# kezpad_SCH.net
KiCad netlist of a schematic drawn in EasyEDA
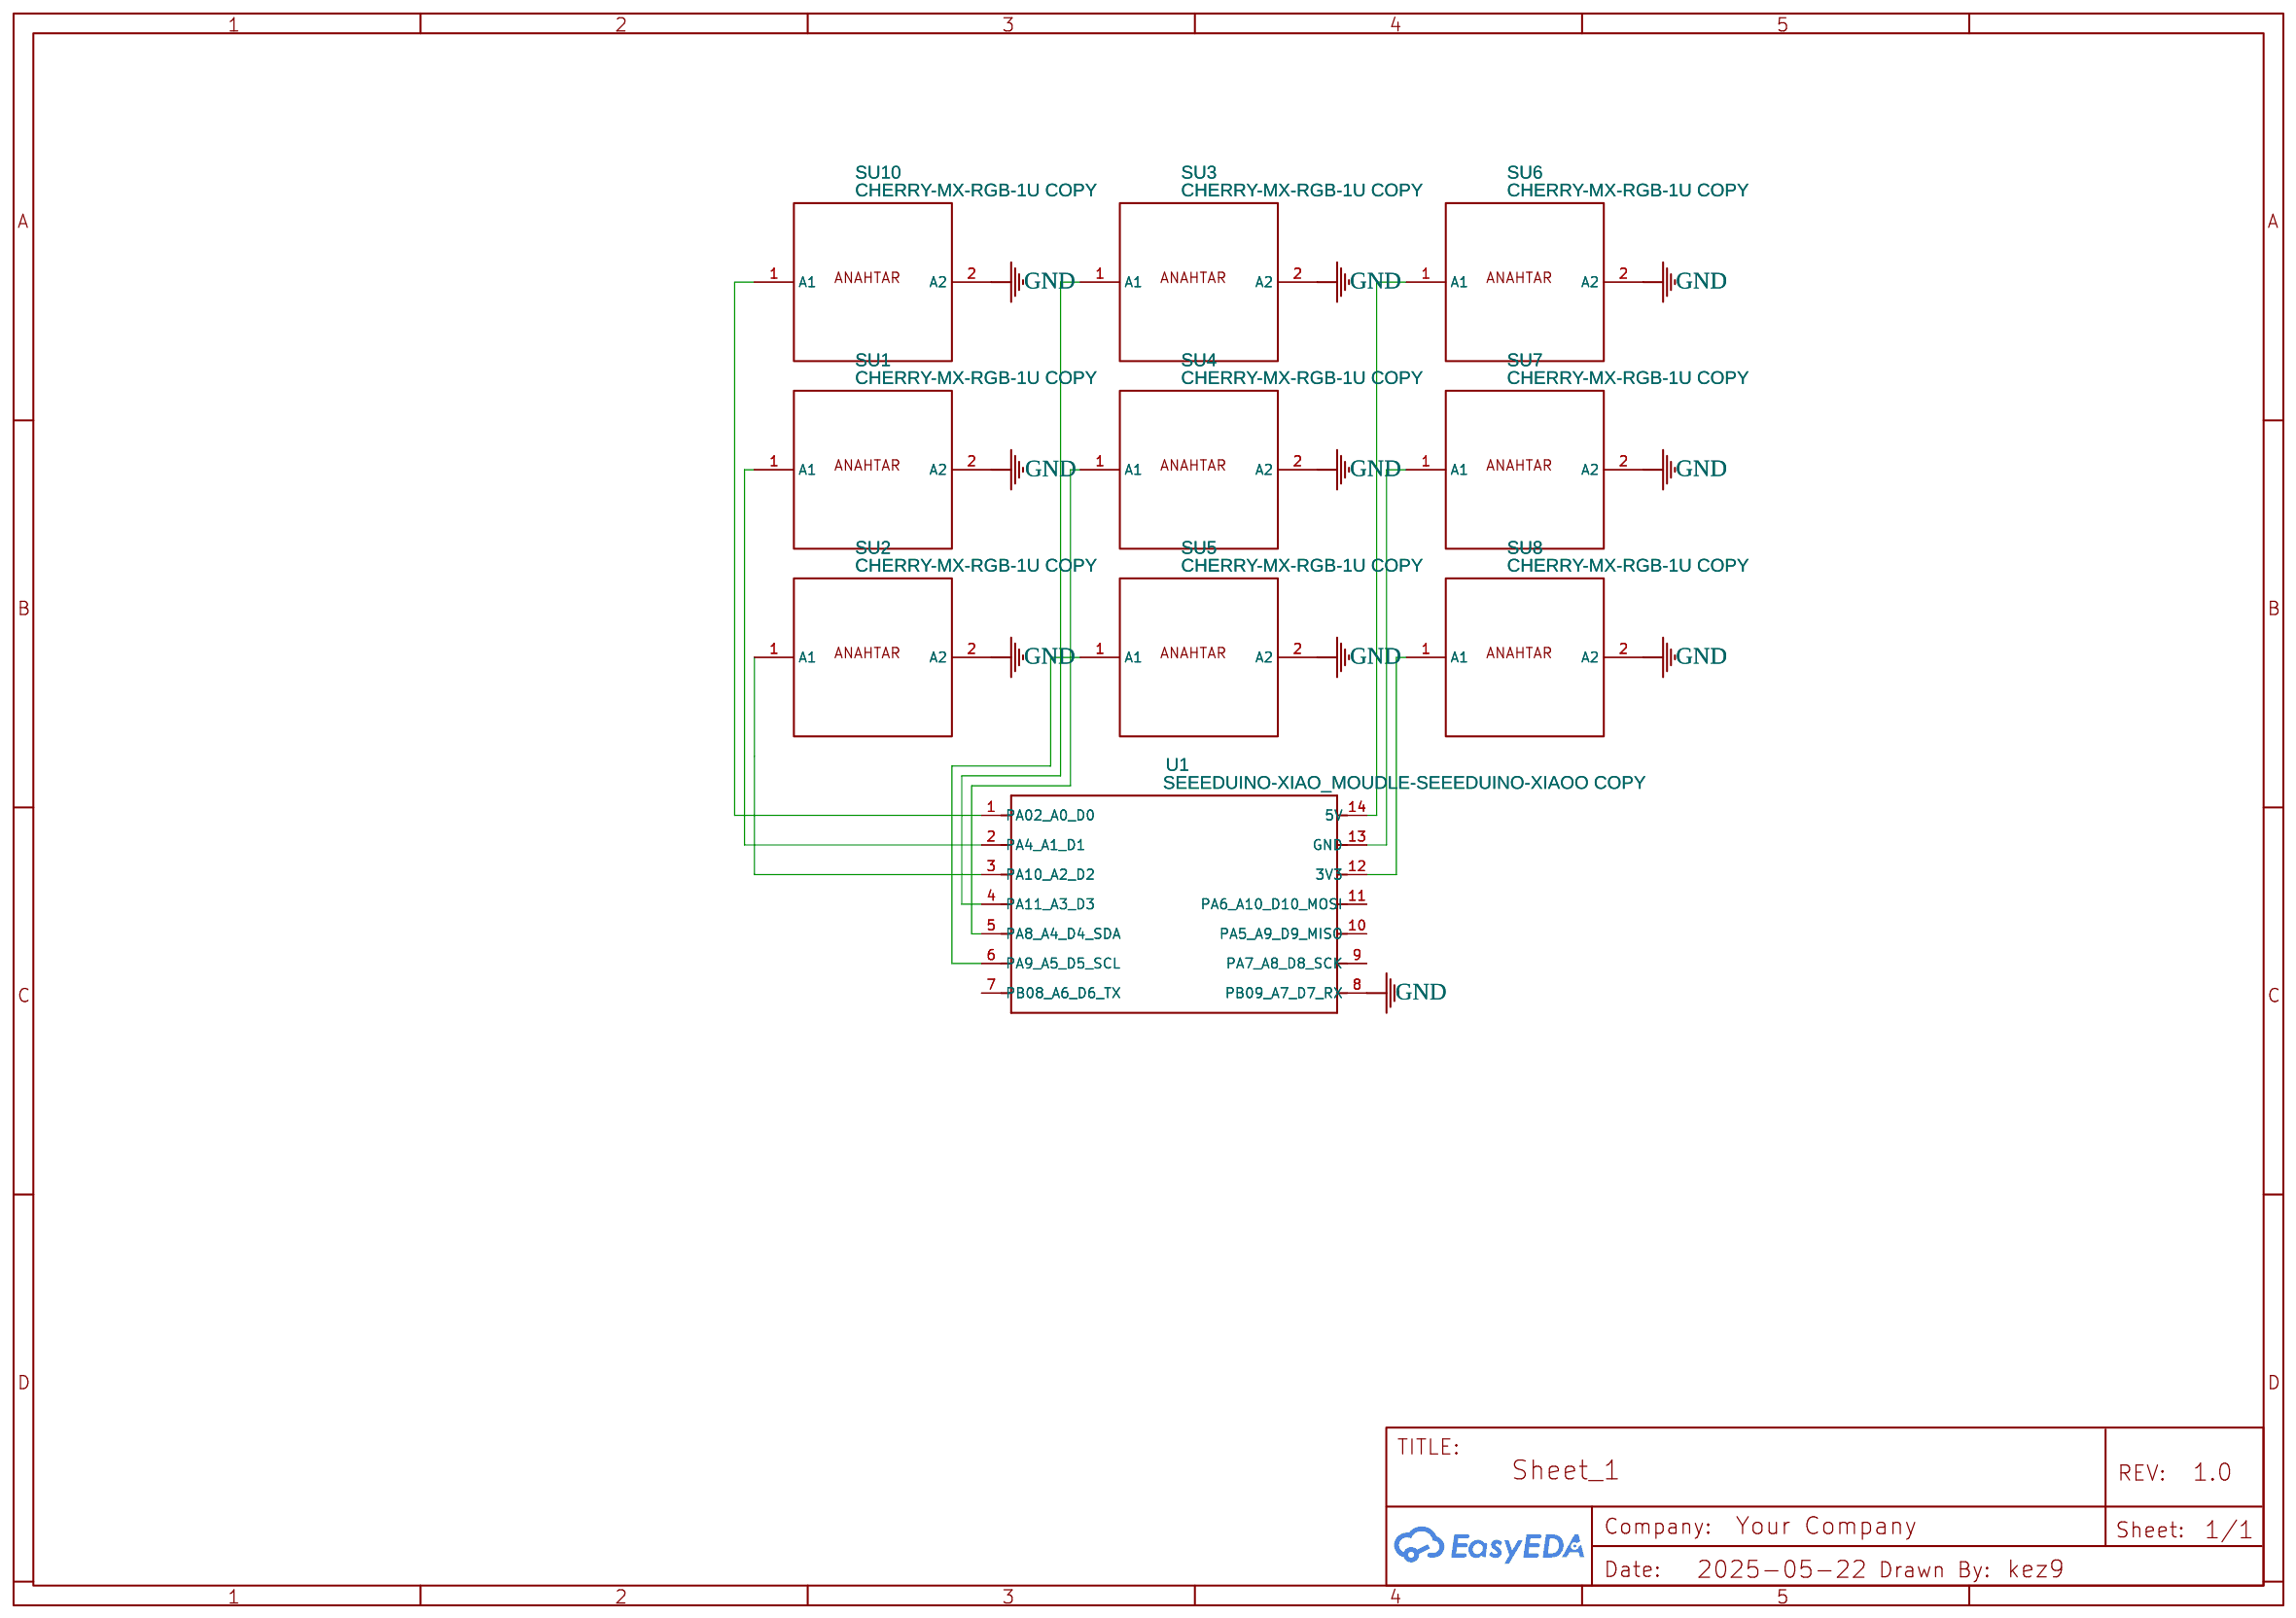
[diagram p0: schematic sheet]

(export (version "E")
  (design (tool "Eeschema 10.0.6"))
  (components
    (comp (ref "SU1") (value "CHERRY-MX-RGB-1U COPY") (libsource (lib "") (part "CHERRY-MX-RGB-1U COPY")))
    (comp (ref "SU2") (value "CHERRY-MX-RGB-1U COPY") (libsource (lib "") (part "CHERRY-MX-RGB-1U COPY")))
    (comp (ref "SU3") (value "CHERRY-MX-RGB-1U COPY") (libsource (lib "") (part "CHERRY-MX-RGB-1U COPY")))
    (comp (ref "SU4") (value "CHERRY-MX-RGB-1U COPY") (libsource (lib "") (part "CHERRY-MX-RGB-1U COPY")))
    (comp (ref "SU5") (value "CHERRY-MX-RGB-1U COPY") (libsource (lib "") (part "CHERRY-MX-RGB-1U COPY")))
    (comp (ref "SU6") (value "CHERRY-MX-RGB-1U COPY") (libsource (lib "") (part "CHERRY-MX-RGB-1U COPY")))
    (comp (ref "SU7") (value "CHERRY-MX-RGB-1U COPY") (libsource (lib "") (part "CHERRY-MX-RGB-1U COPY")))
    (comp (ref "SU8") (value "CHERRY-MX-RGB-1U COPY") (libsource (lib "") (part "CHERRY-MX-RGB-1U COPY")))
    (comp (ref "SU10") (value "CHERRY-MX-RGB-1U COPY") (libsource (lib "") (part "CHERRY-MX-RGB-1U COPY")))
    (comp (ref "U1")
      (value "SEEEDUINO-XIAO_MOUDLE-SEEEDUINO-XIAOO COPY")
      (libsource (lib "") (part "SEEEDUINO-XIAO_MOUDLE-SEEEDUINO-XIAOO COPY"))
    )
  )
  (nets
    (net (code "1") (name "GND") (class "Default")
      (node (ref "SU1") (pin "2") (pinfunction "A2_2") (pintype "unspecified"))
      (node (ref "SU10") (pin "2") (pinfunction "A2_2") (pintype "unspecified"))
      (node (ref "SU2") (pin "2") (pinfunction "A2_2") (pintype "unspecified"))
      (node (ref "SU3") (pin "2") (pinfunction "A2_2") (pintype "unspecified"))
      (node (ref "SU4") (pin "2") (pinfunction "A2_2") (pintype "unspecified"))
      (node (ref "SU5") (pin "2") (pinfunction "A2_2") (pintype "unspecified"))
      (node (ref "SU6") (pin "2") (pinfunction "A2_2") (pintype "unspecified"))
      (node (ref "SU7") (pin "2") (pinfunction "A2_2") (pintype "unspecified"))
      (node (ref "SU8") (pin "2") (pinfunction "A2_2") (pintype "unspecified"))
      (node (ref "U1") (pin "8") (pinfunction "PB09_A7_D7_RX_8") (pintype "bidirectional"))
    )
    (net (code "2") (name "Net-(SU1-A1)") (class "Default")
      (node (ref "SU1") (pin "1") (pinfunction "A1_1") (pintype "unspecified"))
      (node (ref "U1") (pin "2") (pinfunction "PA4_A1_D1_2") (pintype "bidirectional"))
    )
    (net (code "3") (name "Net-(SU2-A1)") (class "Default")
      (node (ref "SU2") (pin "1") (pinfunction "A1_1") (pintype "unspecified"))
      (node (ref "U1") (pin "3") (pinfunction "PA10_A2_D2_3") (pintype "bidirectional"))
    )
    (net (code "4") (name "Net-(SU3-A1)") (class "Default")
      (node (ref "SU3") (pin "1") (pinfunction "A1_1") (pintype "unspecified"))
      (node (ref "U1") (pin "4") (pinfunction "PA11_A3_D3_4") (pintype "bidirectional"))
    )
    (net (code "5") (name "Net-(SU4-A1)") (class "Default")
      (node (ref "SU4") (pin "1") (pinfunction "A1_1") (pintype "unspecified"))
      (node (ref "U1") (pin "5") (pinfunction "PA8_A4_D4_SDA_5") (pintype "bidirectional"))
    )
    (net (code "6") (name "Net-(SU5-A1)") (class "Default")
      (node (ref "SU5") (pin "1") (pinfunction "A1_1") (pintype "unspecified"))
      (node (ref "U1") (pin "6") (pinfunction "PA9_A5_D5_SCL_6") (pintype "bidirectional"))
    )
    (net (code "7") (name "Net-(SU6-A1)") (class "Default")
      (node (ref "SU6") (pin "1") (pinfunction "A1_1") (pintype "unspecified"))
      (node (ref "U1") (pin "14") (pinfunction "5V_14") (pintype "bidirectional"))
    )
    (net (code "8") (name "Net-(SU7-A1)") (class "Default")
      (node (ref "SU7") (pin "1") (pinfunction "A1_1") (pintype "unspecified"))
      (node (ref "U1") (pin "13") (pinfunction "GND_13") (pintype "bidirectional"))
    )
    (net (code "9") (name "Net-(SU8-A1)") (class "Default")
      (node (ref "SU8") (pin "1") (pinfunction "A1_1") (pintype "unspecified"))
      (node (ref "U1") (pin "12") (pinfunction "3V3_12") (pintype "bidirectional"))
    )
    (net (code "10") (name "Net-(SU10-A1)") (class "Default")
      (node (ref "SU10") (pin "1") (pinfunction "A1_1") (pintype "unspecified"))
      (node (ref "U1") (pin "1") (pinfunction "PA02_A0_D0_1") (pintype "bidirectional"))
    )
    (net (code "11") (name "unconnected-(U1-PA5_A9_D9_MISO-Pad10)") (class "Default")
      (node (ref "U1") (pin "10") (pinfunction "PA5_A9_D9_MISO_10") (pintype "bidirectional"))
    )
    (net (code "12") (name "unconnected-(U1-PA6_A10_D10_MOSI-Pad11)") (class "Default")
      (node (ref "U1") (pin "11") (pinfunction "PA6_A10_D10_MOSI_11") (pintype "bidirectional"))
    )
    (net (code "13") (name "unconnected-(U1-PA7_A8_D8_SCK-Pad9)") (class "Default")
      (node (ref "U1") (pin "9") (pinfunction "PA7_A8_D8_SCK_9") (pintype "bidirectional"))
    )
    (net (code "14") (name "unconnected-(U1-PB08_A6_D6_TX-Pad7)") (class "Default")
      (node (ref "U1") (pin "7") (pinfunction "PB08_A6_D6_TX_7") (pintype "bidirectional"))
    )
  )
)
